# atmega_328p_blink.net
KiCad netlist of a schematic drawn in EAGLE
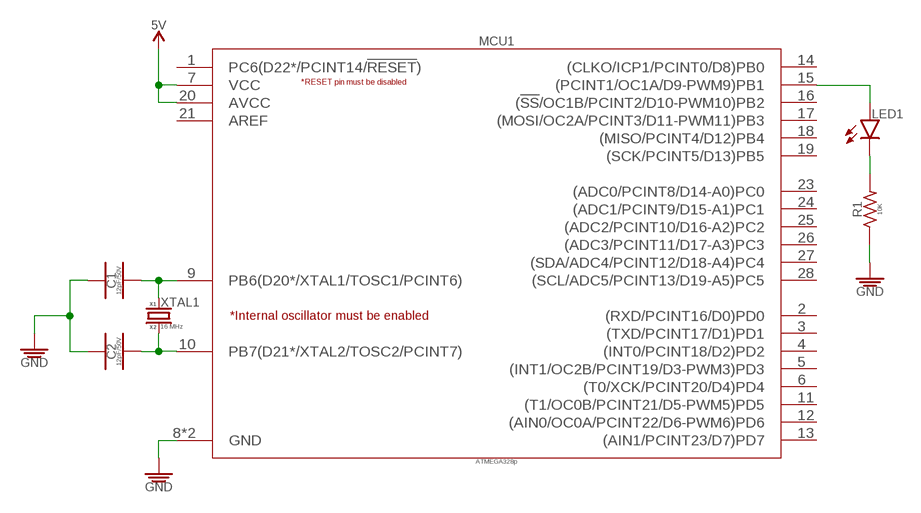
[diagram p0: schematic, sheet 1]

(export (version "E")
  (design (tool "Eeschema 10.0.6"))
  (components
    (comp (ref "C1")
      (value "12pF/50V")
      (footprint "eagle-import:_CER_PTH_LS2.5_L4-W2.5-H5.58")
      (fields (field (name "MFR") "Vishay BC Components") (field (name "MPN") "K120J15C0GF5TL2"))
      (libsource (lib "eagle-import") (part "12PF_PTH-CER_50V-5%"))
    )
    (comp (ref "C2")
      (value "12pF/50V")
      (footprint "eagle-import:_CER_PTH_LS2.5_L4-W2.5-H5.58")
      (fields (field (name "MFR") "Vishay BC Components") (field (name "MPN") "K120J15C0GF5TL2"))
      (libsource (lib "eagle-import") (part "12PF_PTH-CER_50V-5%"))
    )
    (comp (ref "LED1")
      (value "LED_PTH_T-1_3/4_5MM_NO-COLOR")
      (footprint "eagle-import:LED_PTH_T-1_3_4_5MM")
      (libsource (lib "eagle-import") (part "LED_PTH_T-1_3/4_5MM_NO-COLOR"))
    )
    (comp (ref "MCU1")
      (value "ATMEGA328p")
      (footprint "eagle-import:DIP762W53P254L3467H472Q28B")
      (fields (field (name "MFR") "Microchip Technology") (field (name "MPN") "ATMEGA328P-PU"))
      (libsource (lib "eagle-import") (part "ATMEGA328P-28_28-PDIP_8BIT_32KB"))
    )
    (comp (ref "R1")
      (value "10K")
      (footprint "eagle-import:RESAD990W55L630D240B")
      (fields (field (name "MFR") "Yageo") (field (name "MPN") "CFR-25JB-52-10K"))
      (libsource (lib "eagle-import") (part "10KΩ_PTH-207/10_1/4W-5%"))
    )
    (comp (ref "XTAL1")
      (value "16 MHz")
      (footprint "eagle-import:HC-49_US")
      (fields (field (name "MFR") "Abracon LLC") (field (name "MPN") "ABL-16.000MHZ-B2"))
      (libsource (lib "eagle-import") (part "CRYSTAL_ABL_16MHZ_18PF"))
    )
  )
  (nets
    (net (code "1") (name "5V") (class "Default")
      (node (ref "MCU1") (pin "20") (pinfunction "AVCC_20") (pintype "power_in"))
      (node (ref "MCU1") (pin "7") (pinfunction "VCC_7") (pintype "power_in"))
    )
    (net (code "2") (name "GND") (class "Default")
      (node (ref "C1") (pin "P$1") (pinfunction "1_P$1") (pintype "passive"))
      (node (ref "C2") (pin "P$1") (pinfunction "1_P$1") (pintype "passive"))
      (node (ref "MCU1") (pin "22") (pinfunction "GND_22") (pintype "power_in"))
      (node (ref "MCU1") (pin "8") (pinfunction "GND_8") (pintype "power_in"))
      (node (ref "R1") (pin "1") (pinfunction "1_1") (pintype "passive"))
    )
    (net (code "3") (name "Net-(C1-2)") (class "Default")
      (node (ref "C1") (pin "P$2") (pinfunction "2_P$2") (pintype "passive"))
      (node (ref "MCU1") (pin "9") (pinfunction "PB6(D20*/XTAL1/TOSC1/PCINT6)_9") (pintype "bidirectional"))
      (node (ref "XTAL1") (pin "P$1") (pinfunction "XTAL1_P$1") (pintype "passive"))
    )
    (net (code "4") (name "Net-(C2-2)") (class "Default")
      (node (ref "C2") (pin "P$2") (pinfunction "2_P$2") (pintype "passive"))
      (node (ref "MCU1") (pin "10") (pinfunction "PB7(D21*/XTAL2/TOSC2/PCINT7)_10") (pintype "bidirectional"))
      (node (ref "XTAL1") (pin "P$2") (pinfunction "XTAL2_P$2") (pintype "passive"))
    )
    (net (code "5") (name "Net-(LED1-PadK)") (class "Default")
      (node (ref "LED1") (pin "K") (pinfunction "K_K") (pintype "passive"))
      (node (ref "R1") (pin "2") (pinfunction "2_2") (pintype "passive"))
    )
    (net (code "6") (name "Net-(MCU1-(PCINT1{slash}OC1A{slash}D9-PWM9)PB1)") (class "Default")
      (node (ref "LED1") (pin "A") (pinfunction "A_A") (pintype "passive"))
      (node (ref "MCU1") (pin "15") (pinfunction "(PCINT1/OC1A/D9-PWM9)PB1_15") (pintype "bidirectional"))
    )
    (net (code "7") (name "unconnected-(MCU1-(ADC0{slash}PCINT8{slash}D14-A0)PC0-Pad23)") (class "Default")
      (node (ref "MCU1") (pin "23") (pinfunction "(ADC0/PCINT8/D14-A0)PC0_23") (pintype "bidirectional"))
    )
    (net (code "8") (name "unconnected-(MCU1-(ADC1{slash}PCINT9{slash}D15-A1)PC1-Pad24)") (class "Default")
      (node (ref "MCU1") (pin "24") (pinfunction "(ADC1/PCINT9/D15-A1)PC1_24") (pintype "bidirectional"))
    )
    (net (code "9") (name "unconnected-(MCU1-(ADC2{slash}PCINT10{slash}D16-A2)PC2-Pad25)") (class "Default")
      (node (ref "MCU1") (pin "25") (pinfunction "(ADC2/PCINT10/D16-A2)PC2_25") (pintype "bidirectional"))
    )
    (net (code "10") (name "unconnected-(MCU1-(ADC3{slash}PCINT11{slash}D17-A3)PC3-Pad26)") (class "Default")
      (node (ref "MCU1") (pin "26") (pinfunction "(ADC3/PCINT11/D17-A3)PC3_26") (pintype "bidirectional"))
    )
    (net (code "11") (name "unconnected-(MCU1-(AIN0{slash}OC0A{slash}PCINT22{slash}D6-PWM6)PD6-Pad12)") (class "Default")
      (node (ref "MCU1") (pin "12") (pinfunction "(AIN0/OC0A/PCINT22/D6-PWM6)PD6_12") (pintype "bidirectional"))
    )
    (net (code "12") (name "unconnected-(MCU1-(AIN1{slash}PCINT23{slash}D7)PD7-Pad13)") (class "Default")
      (node (ref "MCU1") (pin "13") (pinfunction "(AIN1/PCINT23/D7)PD7_13") (pintype "bidirectional"))
    )
    (net (code "13") (name "unconnected-(MCU1-(CLKO{slash}ICP1{slash}PCINT0{slash}D8)PB0-Pad14)") (class "Default")
      (node (ref "MCU1") (pin "14") (pinfunction "(CLKO/ICP1/PCINT0/D8)PB0_14") (pintype "bidirectional"))
    )
    (net (code "14") (name "unconnected-(MCU1-(INT0{slash}PCINT18{slash}D2)PD2-Pad4)") (class "Default")
      (node (ref "MCU1") (pin "4") (pinfunction "(INT0/PCINT18/D2)PD2_4") (pintype "bidirectional"))
    )
    (net (code "15") (name "unconnected-(MCU1-(INT1{slash}OC2B{slash}PCINT19{slash}D3-PWM3)PD3-Pad5)") (class "Default")
      (node (ref "MCU1") (pin "5") (pinfunction "(INT1/OC2B/PCINT19/D3-PWM3)PD3_5") (pintype "bidirectional"))
    )
    (net (code "16") (name "unconnected-(MCU1-(MISO{slash}PCINT4{slash}D12)PB4-Pad18)") (class "Default")
      (node (ref "MCU1") (pin "18") (pinfunction "(MISO/PCINT4/D12)PB4_18") (pintype "bidirectional"))
    )
    (net (code "17") (name "unconnected-(MCU1-(MOSI{slash}OC2A{slash}PCINT3{slash}D11-PWM11)PB3-Pad17)") (class "Default")
      (node (ref "MCU1") (pin "17") (pinfunction "(MOSI/OC2A/PCINT3/D11-PWM11)PB3_17") (pintype "bidirectional"))
    )
    (net (code "18") (name "unconnected-(MCU1-(RXD{slash}PCINT16{slash}D0)PD0-Pad2)") (class "Default")
      (node (ref "MCU1") (pin "2") (pinfunction "(RXD/PCINT16/D0)PD0_2") (pintype "bidirectional"))
    )
    (net (code "19") (name "unconnected-(MCU1-(SCK{slash}PCINT5{slash}D13)PB5-Pad19)") (class "Default")
      (node (ref "MCU1") (pin "19") (pinfunction "(SCK/PCINT5/D13)PB5_19") (pintype "bidirectional"))
    )
    (net (code "20") (name "unconnected-(MCU1-(SCL{slash}ADC5{slash}PCINT13{slash}D19-A5)PC5-Pad28)") (class "Default")
      (node (ref "MCU1") (pin "28") (pinfunction "(SCL/ADC5/PCINT13/D19-A5)PC5_28") (pintype "bidirectional"))
    )
    (net (code "21") (name "unconnected-(MCU1-(SDA{slash}ADC4{slash}PCINT12{slash}D18-A4)PC4-Pad27)") (class "Default")
      (node (ref "MCU1") (pin "27") (pinfunction "(SDA/ADC4/PCINT12/D18-A4)PC4_27") (pintype "bidirectional"))
    )
    (net (code "22") (name "unconnected-(MCU1-(T0{slash}XCK{slash}PCINT20{slash}D4)PD4-Pad6)") (class "Default")
      (node (ref "MCU1") (pin "6") (pinfunction "(T0/XCK/PCINT20/D4)PD4_6") (pintype "bidirectional"))
    )
    (net (code "23") (name "unconnected-(MCU1-(T1{slash}OC0B{slash}PCINT21{slash}D5-PWM5)PD5-Pad11)") (class "Default")
      (node (ref "MCU1") (pin "11") (pinfunction "(T1/OC0B/PCINT21/D5-PWM5)PD5_11") (pintype "bidirectional"))
    )
    (net (code "24") (name "unconnected-(MCU1-(TXD{slash}PCINT17{slash}D1)PD1-Pad3)") (class "Default")
      (node (ref "MCU1") (pin "3") (pinfunction "(TXD/PCINT17/D1)PD1_3") (pintype "bidirectional"))
    )
    (net (code "25") (name "unconnected-(MCU1-(~{SS}{slash}OC1B{slash}PCINT2{slash}D10-PWM10)PB2-Pad16)") (class "Default")
      (node (ref "MCU1") (pin "16") (pinfunction "(~{SS}/OC1B/PCINT2/D10-PWM10)PB2_16") (pintype "bidirectional"))
    )
    (net (code "26") (name "unconnected-(MCU1-AREF-Pad21)") (class "Default")
      (node (ref "MCU1") (pin "21") (pinfunction "AREF_21") (pintype "passive"))
    )
    (net (code "27") (name "unconnected-(MCU1-PC6(D22*{slash}PCINT14{slash}~{RESET})-Pad1)") (class "Default")
      (node (ref "MCU1") (pin "1") (pinfunction "PC6(D22*/PCINT14/~{RESET})_1") (pintype "bidirectional"))
    )
  )
)
